# EMG_v0_0.net
KiCad netlist of a schematic drawn in EasyEDA Pro
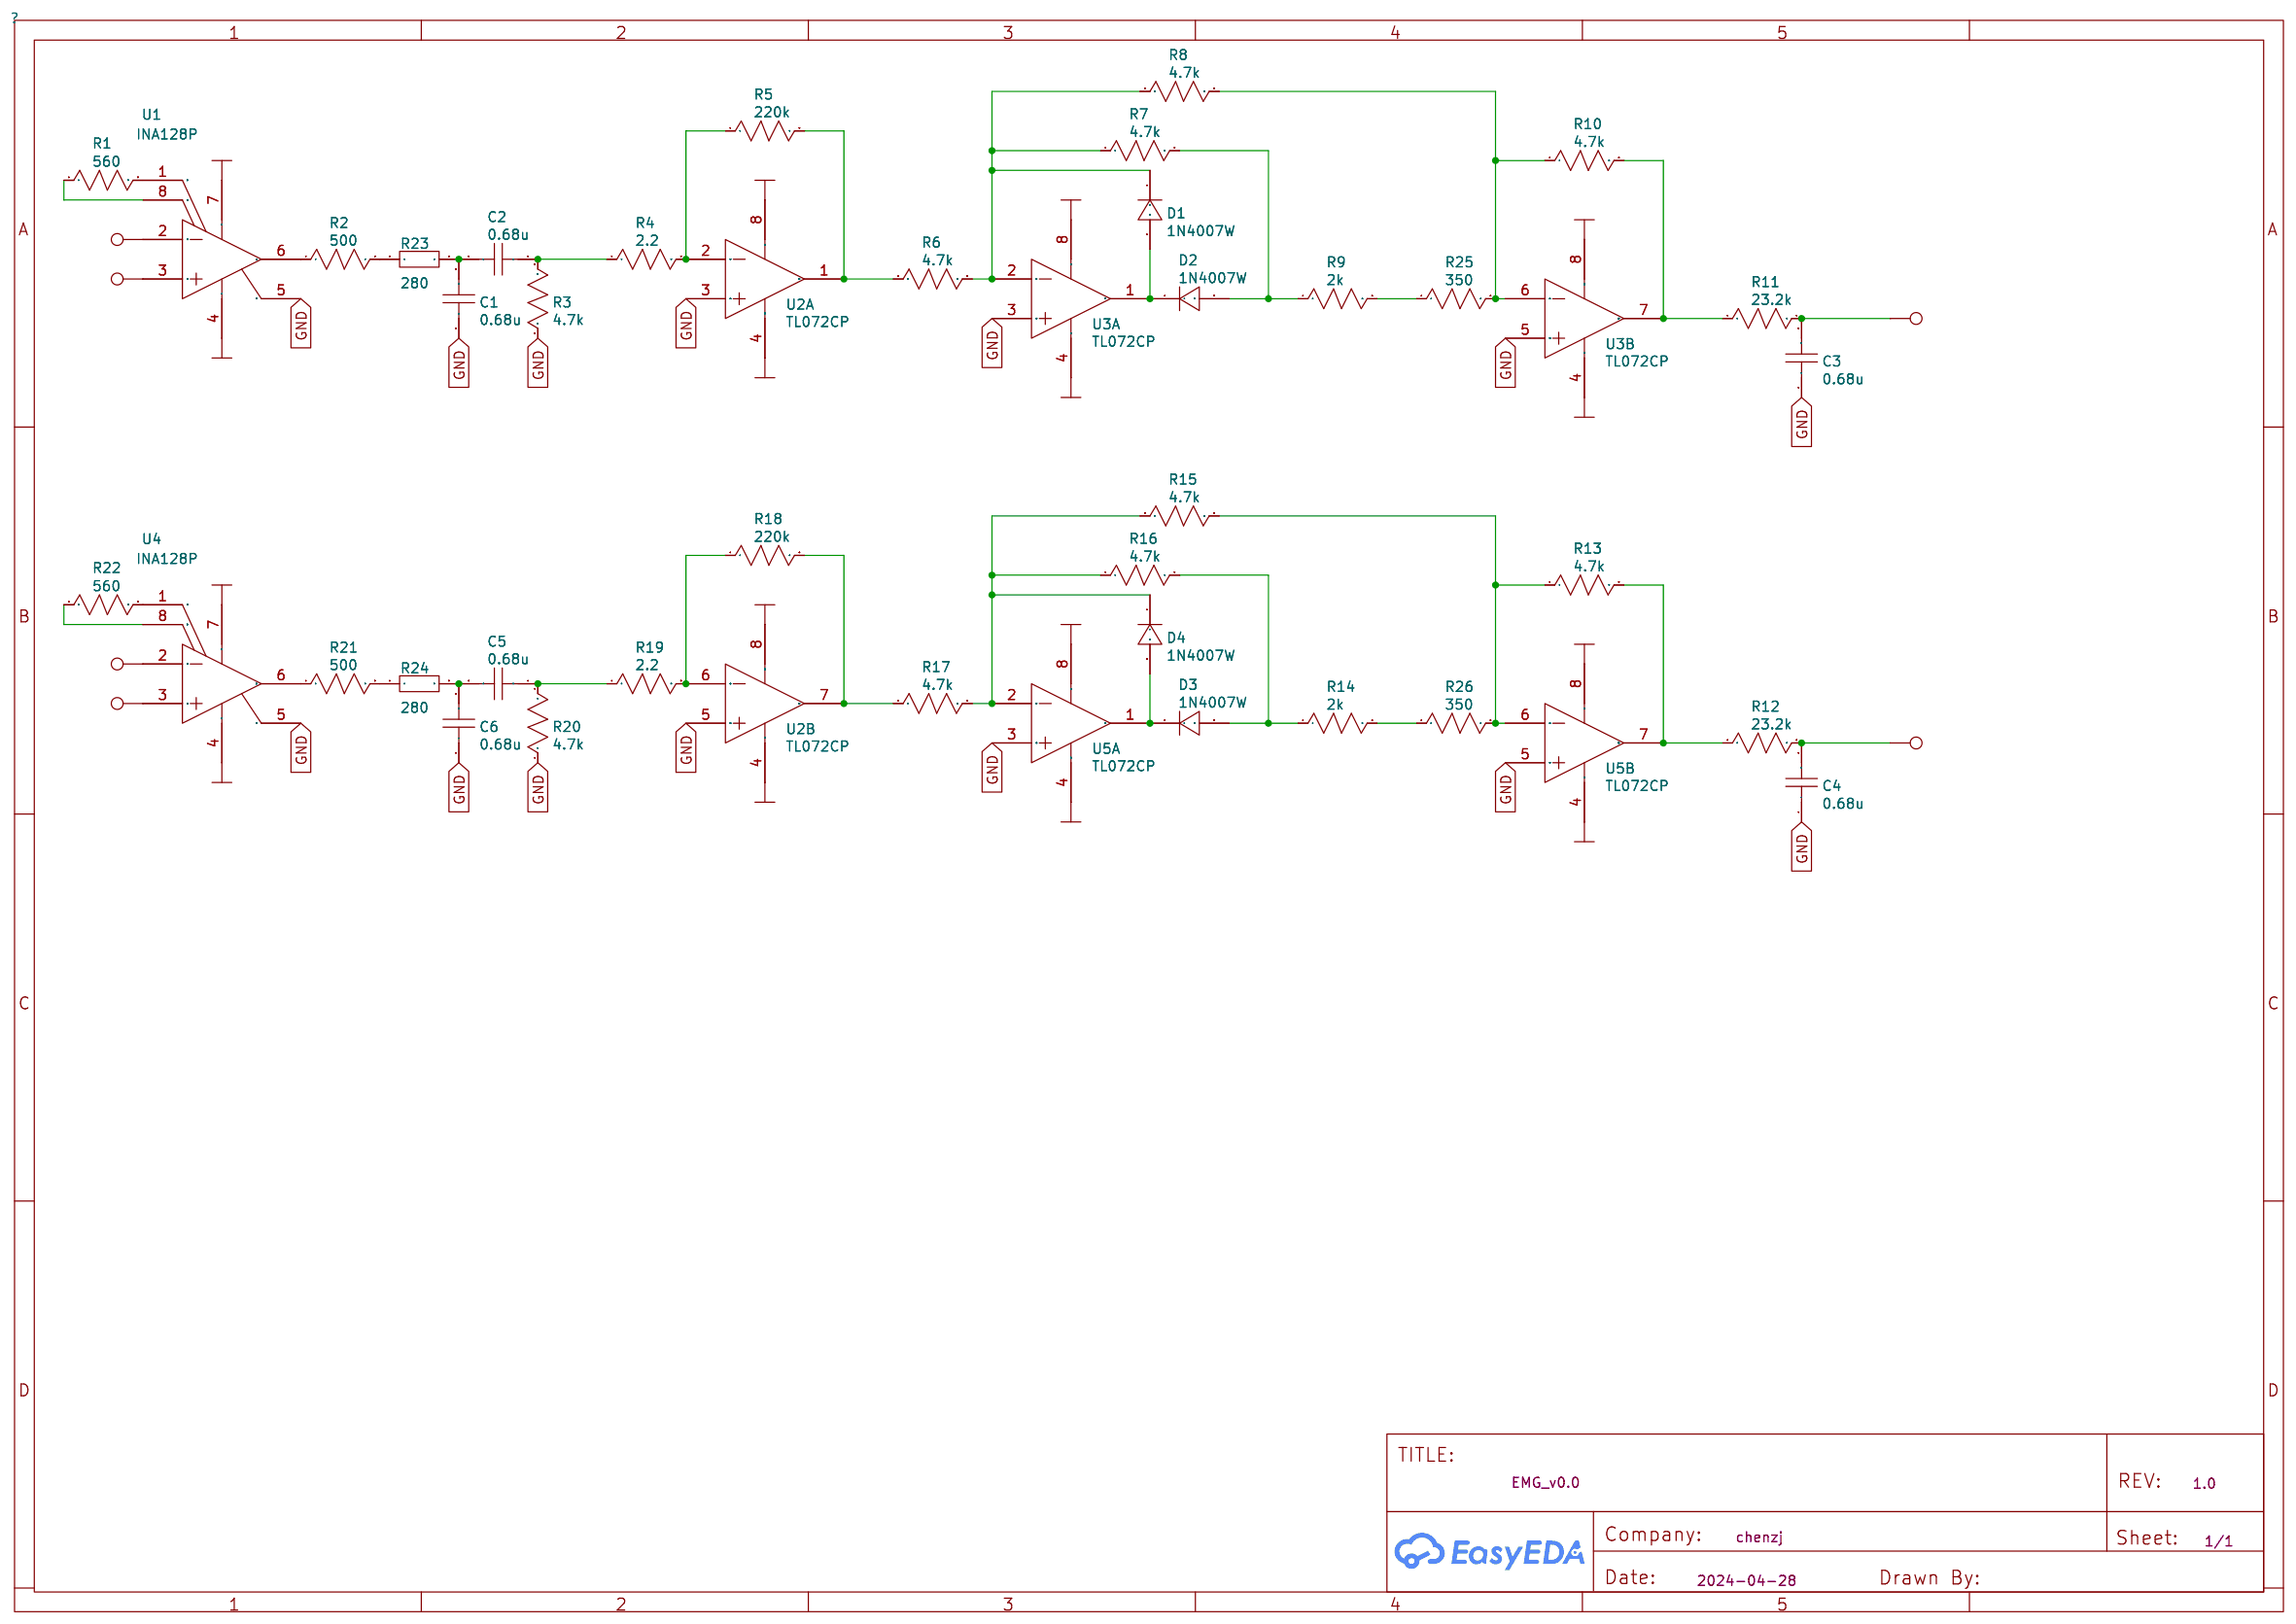
[diagram p0: schematic sheet]

(export (version "E")
  (design (tool "Eeschema 10.0.6"))
  (components
    (comp (ref "C1")
      (value "0.68u")
      (footprint "easyedapro:C0603")
      (libsource (lib "easyedapro") (part "0.68u"))
    )
    (comp (ref "C2")
      (value "0.68u")
      (footprint "easyedapro:C0603")
      (libsource (lib "easyedapro") (part "0.68u"))
    )
    (comp (ref "C3")
      (value "0.68u")
      (footprint "easyedapro:C0603")
      (libsource (lib "easyedapro") (part "680n"))
    )
    (comp (ref "C4")
      (value "0.68u")
      (footprint "easyedapro:C0603")
      (libsource (lib "easyedapro") (part "680n"))
    )
    (comp (ref "C5")
      (value "0.68u")
      (footprint "easyedapro:C0603")
      (libsource (lib "easyedapro") (part "0.68u"))
    )
    (comp (ref "C6")
      (value "0.68u")
      (footprint "easyedapro:C0603")
      (libsource (lib "easyedapro") (part "0.68u"))
    )
    (comp (ref "D1")
      (value "1N4007W")
      (footprint "easyedapro:SOD-123_L2.8-W1.8-LS3.7-RD")
      (fields (field (name "Manufacturer") "BLUE ROCKET"))
      (libsource (lib "easyedapro") (part "1N4007W"))
    )
    (comp (ref "D2")
      (value "1N4007W")
      (footprint "easyedapro:SOD-123_L2.8-W1.8-LS3.7-RD")
      (fields (field (name "Manufacturer") "BLUE ROCKET"))
      (libsource (lib "easyedapro") (part "1N4007W"))
    )
    (comp (ref "D3")
      (value "1N4007W")
      (footprint "easyedapro:SOD-123_L2.8-W1.8-LS3.7-RD")
      (fields (field (name "Manufacturer") "BLUE ROCKET"))
      (libsource (lib "easyedapro") (part "1N4007W"))
    )
    (comp (ref "D4")
      (value "1N4007W")
      (footprint "easyedapro:SOD-123_L2.8-W1.8-LS3.7-RD")
      (fields (field (name "Manufacturer") "BLUE ROCKET"))
      (libsource (lib "easyedapro") (part "1N4007W"))
    )
    (comp (ref "R1") (value "560") (footprint "easyedapro:R0603") (libsource (lib "easyedapro") (part "560")))
    (comp (ref "R2") (value "500") (footprint "easyedapro:R0603") (libsource (lib "easyedapro") (part "780")))
    (comp (ref "R3")
      (value "4.7k")
      (footprint "easyedapro:R0603")
      (libsource (lib "easyedapro") (part "4.7k"))
    )
    (comp (ref "R4") (value "2.2") (footprint "easyedapro:R0603") (libsource (lib "easyedapro") (part "2.2")))
    (comp (ref "R5")
      (value "220k")
      (footprint "easyedapro:R0603")
      (libsource (lib "easyedapro") (part "220k"))
    )
    (comp (ref "R6")
      (value "4.7k")
      (footprint "easyedapro:R0603")
      (libsource (lib "easyedapro") (part "4.7k"))
    )
    (comp (ref "R7")
      (value "4.7k")
      (footprint "easyedapro:R0603")
      (libsource (lib "easyedapro") (part "4.7k"))
    )
    (comp (ref "R8")
      (value "4.7k")
      (footprint "easyedapro:R0603")
      (libsource (lib "easyedapro") (part "4.7k"))
    )
    (comp (ref "R9")
      (value "2k")
      (footprint "easyedapro:R0603")
      (libsource (lib "easyedapro") (part "2.35k"))
    )
    (comp (ref "R10")
      (value "4.7k")
      (footprint "easyedapro:R0603")
      (libsource (lib "easyedapro") (part "4.7k"))
    )
    (comp (ref "R11")
      (value "23.2k")
      (footprint "easyedapro:R0603")
      (libsource (lib "easyedapro") (part "23.2k"))
    )
    (comp (ref "R12")
      (value "23.2k")
      (footprint "easyedapro:R0603")
      (libsource (lib "easyedapro") (part "23.2k"))
    )
    (comp (ref "R13")
      (value "4.7k")
      (footprint "easyedapro:R0603")
      (libsource (lib "easyedapro") (part "4.7k"))
    )
    (comp (ref "R14")
      (value "2k")
      (footprint "easyedapro:R0603")
      (libsource (lib "easyedapro") (part "2.35k"))
    )
    (comp (ref "R15")
      (value "4.7k")
      (footprint "easyedapro:R0603")
      (libsource (lib "easyedapro") (part "4.7k"))
    )
    (comp (ref "R16")
      (value "4.7k")
      (footprint "easyedapro:R0603")
      (libsource (lib "easyedapro") (part "4.7k"))
    )
    (comp (ref "R17")
      (value "4.7k")
      (footprint "easyedapro:R0603")
      (libsource (lib "easyedapro") (part "4.7k"))
    )
    (comp (ref "R18")
      (value "220k")
      (footprint "easyedapro:R0603")
      (libsource (lib "easyedapro") (part "220k"))
    )
    (comp (ref "R19")
      (value "2.2")
      (footprint "easyedapro:R0603")
      (libsource (lib "easyedapro") (part "2.2"))
    )
    (comp (ref "R20")
      (value "4.7k")
      (footprint "easyedapro:R0603")
      (libsource (lib "easyedapro") (part "4.7k"))
    )
    (comp (ref "R21")
      (value "500")
      (footprint "easyedapro:R0603")
      (libsource (lib "easyedapro") (part "780"))
    )
    (comp (ref "R22")
      (value "560")
      (footprint "easyedapro:R0603")
      (libsource (lib "easyedapro") (part "560"))
    )
    (comp (ref "R23")
      (value "280")
      (footprint "easyedapro:R0201")
      (libsource (lib "easyedapro") (part "Res"))
    )
    (comp (ref "R24")
      (value "280")
      (footprint "easyedapro:R0201")
      (libsource (lib "easyedapro") (part "Res"))
    )
    (comp (ref "R25")
      (value "350")
      (footprint "easyedapro:R0603")
      (libsource (lib "easyedapro") (part "2.35k"))
    )
    (comp (ref "R26")
      (value "350")
      (footprint "easyedapro:R0603")
      (libsource (lib "easyedapro") (part "2.35k"))
    )
    (comp (ref "U1")
      (value "INA128P")
      (footprint "easyedapro:PDIP-8_L9.6-W6.4-P2.54-LS7.9-BL")
      (fields (field (name "Manufacturer") "TI(德州仪器)"))
      (libsource (lib "easyedapro") (part "INA128P"))
    )
    (comp (ref "U2")
      (value "TL072CP")
      (footprint "easyedapro:DIP-8_L9.6-W6.4-P2.54-LS7.6-BL-1")
      (fields (field (name "Manufacturer") "TI(德州仪器)"))
      (libsource (lib "easyedapro") (part "TL072CP"))
    )
    (comp (ref "U3")
      (value "TL072CP")
      (footprint "easyedapro:DIP-8_L9.6-W6.4-P2.54-LS7.6-BL-1")
      (fields (field (name "Manufacturer") "TI(德州仪器)"))
      (libsource (lib "easyedapro") (part "TL072CP"))
    )
    (comp (ref "U4")
      (value "INA128P")
      (footprint "easyedapro:PDIP-8_L9.6-W6.4-P2.54-LS7.9-BL")
      (fields (field (name "Manufacturer") "TI(德州仪器)"))
      (libsource (lib "easyedapro") (part "INA128P"))
    )
    (comp (ref "U5")
      (value "TL072CP")
      (footprint "easyedapro:DIP-8_L9.6-W6.4-P2.54-LS7.6-BL-1")
      (fields (field (name "Manufacturer") "TI(德州仪器)"))
      (libsource (lib "easyedapro") (part "TL072CP"))
    )
  )
  (nets
    (net (code "1") (name "+5V") (class "Default")
      (node (ref "U1") (pin "7") (pinfunction "V+_7") (pintype "unspecified"))
      (node (ref "U2") (pin "8") (pinfunction "VCC+_8") (pintype "unspecified"))
      (node (ref "U3") (pin "8") (pinfunction "VCC+_8") (pintype "unspecified"))
      (node (ref "U4") (pin "7") (pinfunction "V+_7") (pintype "unspecified"))
      (node (ref "U5") (pin "8") (pinfunction "VCC+_8") (pintype "unspecified"))
    )
    (net (code "2") (name "-5V") (class "Default")
      (node (ref "U1") (pin "4") (pinfunction "V-_4") (pintype "unspecified"))
      (node (ref "U2") (pin "4") (pinfunction "VCC-_4") (pintype "unspecified"))
      (node (ref "U3") (pin "4") (pinfunction "VCC-_4") (pintype "unspecified"))
      (node (ref "U4") (pin "4") (pinfunction "V-_4") (pintype "unspecified"))
      (node (ref "U5") (pin "4") (pinfunction "VCC-_4") (pintype "unspecified"))
    )
    (net (code "3") (name "GND") (class "Default")
      (node (ref "C1") (pin "1") (pinfunction "1_1") (pintype "unspecified"))
      (node (ref "C3") (pin "1") (pinfunction "1_1") (pintype "unspecified"))
      (node (ref "C4") (pin "1") (pinfunction "1_1") (pintype "unspecified"))
      (node (ref "C6") (pin "1") (pinfunction "1_1") (pintype "unspecified"))
      (node (ref "R20") (pin "1") (pinfunction "1_1") (pintype "unspecified"))
      (node (ref "R3") (pin "1") (pinfunction "1_1") (pintype "unspecified"))
      (node (ref "U1") (pin "5") (pinfunction "Ref_5") (pintype "unspecified"))
      (node (ref "U2") (pin "3") (pinfunction "IN1+_3") (pintype "unspecified"))
      (node (ref "U2") (pin "5") (pinfunction "IN1+_5") (pintype "unspecified"))
      (node (ref "U3") (pin "3") (pinfunction "IN1+_3") (pintype "unspecified"))
      (node (ref "U3") (pin "5") (pinfunction "IN1+_5") (pintype "unspecified"))
      (node (ref "U4") (pin "5") (pinfunction "Ref_5") (pintype "unspecified"))
      (node (ref "U5") (pin "3") (pinfunction "IN1+_3") (pintype "unspecified"))
      (node (ref "U5") (pin "5") (pinfunction "IN1+_5") (pintype "unspecified"))
    )
    (net (code "4") (name "Net-(C1-Pad2)") (class "Default")
      (node (ref "C1") (pin "2") (pinfunction "2_2") (pintype "unspecified"))
      (node (ref "C2") (pin "2") (pinfunction "2_2") (pintype "unspecified"))
      (node (ref "R23") (pin "2") (pinfunction "2_2") (pintype "input"))
    )
    (net (code "5") (name "Net-(C2-Pad1)") (class "Default")
      (node (ref "C2") (pin "1") (pinfunction "1_1") (pintype "unspecified"))
      (node (ref "R3") (pin "2") (pinfunction "2_2") (pintype "unspecified"))
      (node (ref "R4") (pin "1") (pinfunction "1_1") (pintype "unspecified"))
    )
    (net (code "6") (name "Net-(C5-Pad1)") (class "Default")
      (node (ref "C5") (pin "1") (pinfunction "1_1") (pintype "unspecified"))
      (node (ref "R19") (pin "1") (pinfunction "1_1") (pintype "unspecified"))
      (node (ref "R20") (pin "2") (pinfunction "2_2") (pintype "unspecified"))
    )
    (net (code "7") (name "Net-(C5-Pad2)") (class "Default")
      (node (ref "C5") (pin "2") (pinfunction "2_2") (pintype "unspecified"))
      (node (ref "C6") (pin "2") (pinfunction "2_2") (pintype "unspecified"))
      (node (ref "R24") (pin "2") (pinfunction "2_2") (pintype "input"))
    )
    (net (code "8") (name "Net-(D2-Pad2)") (class "Default")
      (node (ref "D2") (pin "2") (pinfunction "2_2") (pintype "unspecified"))
      (node (ref "R7") (pin "2") (pinfunction "2_2") (pintype "unspecified"))
      (node (ref "R9") (pin "1") (pinfunction "1_1") (pintype "unspecified"))
    )
    (net (code "9") (name "Net-(D3-Pad2)") (class "Default")
      (node (ref "D3") (pin "2") (pinfunction "2_2") (pintype "unspecified"))
      (node (ref "R14") (pin "1") (pinfunction "1_1") (pintype "unspecified"))
      (node (ref "R16") (pin "2") (pinfunction "2_2") (pintype "unspecified"))
    )
    (net (code "10") (name "Net-(R1-Pad1)") (class "Default")
      (node (ref "R1") (pin "1") (pinfunction "1_1") (pintype "unspecified"))
      (node (ref "U1") (pin "8") (pinfunction "RG_8") (pintype "unspecified"))
    )
    (net (code "11") (name "Net-(R1-Pad2)") (class "Default")
      (node (ref "R1") (pin "2") (pinfunction "2_2") (pintype "unspecified"))
      (node (ref "U1") (pin "1") (pinfunction "RG_1") (pintype "unspecified"))
    )
    (net (code "12") (name "Net-(R2-Pad2)") (class "Default")
      (node (ref "R2") (pin "2") (pinfunction "2_2") (pintype "unspecified"))
      (node (ref "R23") (pin "1") (pinfunction "1_1") (pintype "input"))
    )
    (net (code "13") (name "Net-(R14-Pad2)") (class "Default")
      (node (ref "R14") (pin "2") (pinfunction "2_2") (pintype "unspecified"))
      (node (ref "R26") (pin "1") (pinfunction "1_1") (pintype "unspecified"))
    )
    (net (code "14") (name "Net-(R21-Pad2)") (class "Default")
      (node (ref "R21") (pin "2") (pinfunction "2_2") (pintype "unspecified"))
      (node (ref "R24") (pin "1") (pinfunction "1_1") (pintype "input"))
    )
    (net (code "15") (name "Net-(R22-Pad1)") (class "Default")
      (node (ref "R22") (pin "1") (pinfunction "1_1") (pintype "unspecified"))
      (node (ref "U4") (pin "8") (pinfunction "RG_8") (pintype "unspecified"))
    )
    (net (code "16") (name "Net-(R22-Pad2)") (class "Default")
      (node (ref "R22") (pin "2") (pinfunction "2_2") (pintype "unspecified"))
      (node (ref "U4") (pin "1") (pinfunction "RG_1") (pintype "unspecified"))
    )
    (net (code "17") (name "Net-(R25-Pad1)") (class "Default")
      (node (ref "R25") (pin "1") (pinfunction "1_1") (pintype "unspecified"))
      (node (ref "R9") (pin "2") (pinfunction "2_2") (pintype "unspecified"))
    )
    (net (code "18") (name "Net-(U1-VO)") (class "Default")
      (node (ref "R2") (pin "1") (pinfunction "1_1") (pintype "unspecified"))
      (node (ref "U1") (pin "6") (pinfunction "VO_6") (pintype "output"))
    )
    (net (code "19") (name "Net-(U2A-IN1-)") (class "Default")
      (node (ref "R4") (pin "2") (pinfunction "2_2") (pintype "unspecified"))
      (node (ref "R5") (pin "1") (pinfunction "1_1") (pintype "unspecified"))
      (node (ref "U2") (pin "2") (pinfunction "IN1-_2") (pintype "unspecified"))
    )
    (net (code "20") (name "Net-(U2A-OUT1)") (class "Default")
      (node (ref "R5") (pin "2") (pinfunction "2_2") (pintype "unspecified"))
      (node (ref "R6") (pin "1") (pinfunction "1_1") (pintype "unspecified"))
      (node (ref "U2") (pin "1") (pinfunction "OUT1_1") (pintype "output"))
    )
    (net (code "21") (name "Net-(U2B-IN1-)") (class "Default")
      (node (ref "R18") (pin "1") (pinfunction "1_1") (pintype "unspecified"))
      (node (ref "R19") (pin "2") (pinfunction "2_2") (pintype "unspecified"))
      (node (ref "U2") (pin "6") (pinfunction "IN1-_6") (pintype "unspecified"))
    )
    (net (code "22") (name "Net-(U2B-OUT1)") (class "Default")
      (node (ref "R17") (pin "1") (pinfunction "1_1") (pintype "unspecified"))
      (node (ref "R18") (pin "2") (pinfunction "2_2") (pintype "unspecified"))
      (node (ref "U2") (pin "7") (pinfunction "OUT1_7") (pintype "output"))
    )
    (net (code "23") (name "Net-(U3A-IN1-)") (class "Default")
      (node (ref "D1") (pin "1") (pinfunction "1_1") (pintype "unspecified"))
      (node (ref "R6") (pin "2") (pinfunction "2_2") (pintype "unspecified"))
      (node (ref "R7") (pin "1") (pinfunction "1_1") (pintype "unspecified"))
      (node (ref "R8") (pin "1") (pinfunction "1_1") (pintype "unspecified"))
      (node (ref "U3") (pin "2") (pinfunction "IN1-_2") (pintype "unspecified"))
    )
    (net (code "24") (name "Net-(U3A-OUT1)") (class "Default")
      (node (ref "D1") (pin "2") (pinfunction "2_2") (pintype "unspecified"))
      (node (ref "D2") (pin "1") (pinfunction "1_1") (pintype "unspecified"))
      (node (ref "U3") (pin "1") (pinfunction "OUT1_1") (pintype "output"))
    )
    (net (code "25") (name "Net-(U3B-IN1-)") (class "Default")
      (node (ref "R10") (pin "1") (pinfunction "1_1") (pintype "unspecified"))
      (node (ref "R25") (pin "2") (pinfunction "2_2") (pintype "unspecified"))
      (node (ref "R8") (pin "2") (pinfunction "2_2") (pintype "unspecified"))
      (node (ref "U3") (pin "6") (pinfunction "IN1-_6") (pintype "unspecified"))
    )
    (net (code "26") (name "Net-(U3B-OUT1)") (class "Default")
      (node (ref "R10") (pin "2") (pinfunction "2_2") (pintype "unspecified"))
      (node (ref "R11") (pin "1") (pinfunction "1_1") (pintype "unspecified"))
      (node (ref "U3") (pin "7") (pinfunction "OUT1_7") (pintype "output"))
    )
    (net (code "27") (name "Net-(U4-VO)") (class "Default")
      (node (ref "R21") (pin "1") (pinfunction "1_1") (pintype "unspecified"))
      (node (ref "U4") (pin "6") (pinfunction "VO_6") (pintype "output"))
    )
    (net (code "28") (name "Net-(U5A-IN1-)") (class "Default")
      (node (ref "D4") (pin "1") (pinfunction "1_1") (pintype "unspecified"))
      (node (ref "R15") (pin "1") (pinfunction "1_1") (pintype "unspecified"))
      (node (ref "R16") (pin "1") (pinfunction "1_1") (pintype "unspecified"))
      (node (ref "R17") (pin "2") (pinfunction "2_2") (pintype "unspecified"))
      (node (ref "U5") (pin "2") (pinfunction "IN1-_2") (pintype "unspecified"))
    )
    (net (code "29") (name "Net-(U5A-OUT1)") (class "Default")
      (node (ref "D3") (pin "1") (pinfunction "1_1") (pintype "unspecified"))
      (node (ref "D4") (pin "2") (pinfunction "2_2") (pintype "unspecified"))
      (node (ref "U5") (pin "1") (pinfunction "OUT1_1") (pintype "output"))
    )
    (net (code "30") (name "Net-(U5B-IN1-)") (class "Default")
      (node (ref "R13") (pin "1") (pinfunction "1_1") (pintype "unspecified"))
      (node (ref "R15") (pin "2") (pinfunction "2_2") (pintype "unspecified"))
      (node (ref "R26") (pin "2") (pinfunction "2_2") (pintype "unspecified"))
      (node (ref "U5") (pin "6") (pinfunction "IN1-_6") (pintype "unspecified"))
    )
    (net (code "31") (name "Net-(U5B-OUT1)") (class "Default")
      (node (ref "R12") (pin "1") (pinfunction "1_1") (pintype "unspecified"))
      (node (ref "R13") (pin "2") (pinfunction "2_2") (pintype "unspecified"))
      (node (ref "U5") (pin "7") (pinfunction "OUT1_7") (pintype "output"))
    )
    (net (code "32") (name "VIN1+") (class "Default")
      (node (ref "U1") (pin "3") (pinfunction "V+IN_3") (pintype "unspecified"))
    )
    (net (code "33") (name "VIN1-") (class "Default")
      (node (ref "U1") (pin "2") (pinfunction "V-IN_2") (pintype "unspecified"))
    )
    (net (code "34") (name "VIN2+") (class "Default")
      (node (ref "U4") (pin "3") (pinfunction "V+IN_3") (pintype "unspecified"))
    )
    (net (code "35") (name "VIN2-") (class "Default")
      (node (ref "U4") (pin "2") (pinfunction "V-IN_2") (pintype "unspecified"))
    )
    (net (code "36") (name "VOUT1") (class "Default")
      (node (ref "C3") (pin "2") (pinfunction "2_2") (pintype "unspecified"))
      (node (ref "R11") (pin "2") (pinfunction "2_2") (pintype "unspecified"))
    )
    (net (code "37") (name "VOUT2") (class "Default")
      (node (ref "C4") (pin "2") (pinfunction "2_2") (pintype "unspecified"))
      (node (ref "R12") (pin "2") (pinfunction "2_2") (pintype "unspecified"))
    )
  )
)
